# glove-pcb.net
KiCad netlist of a schematic drawn in EAGLE
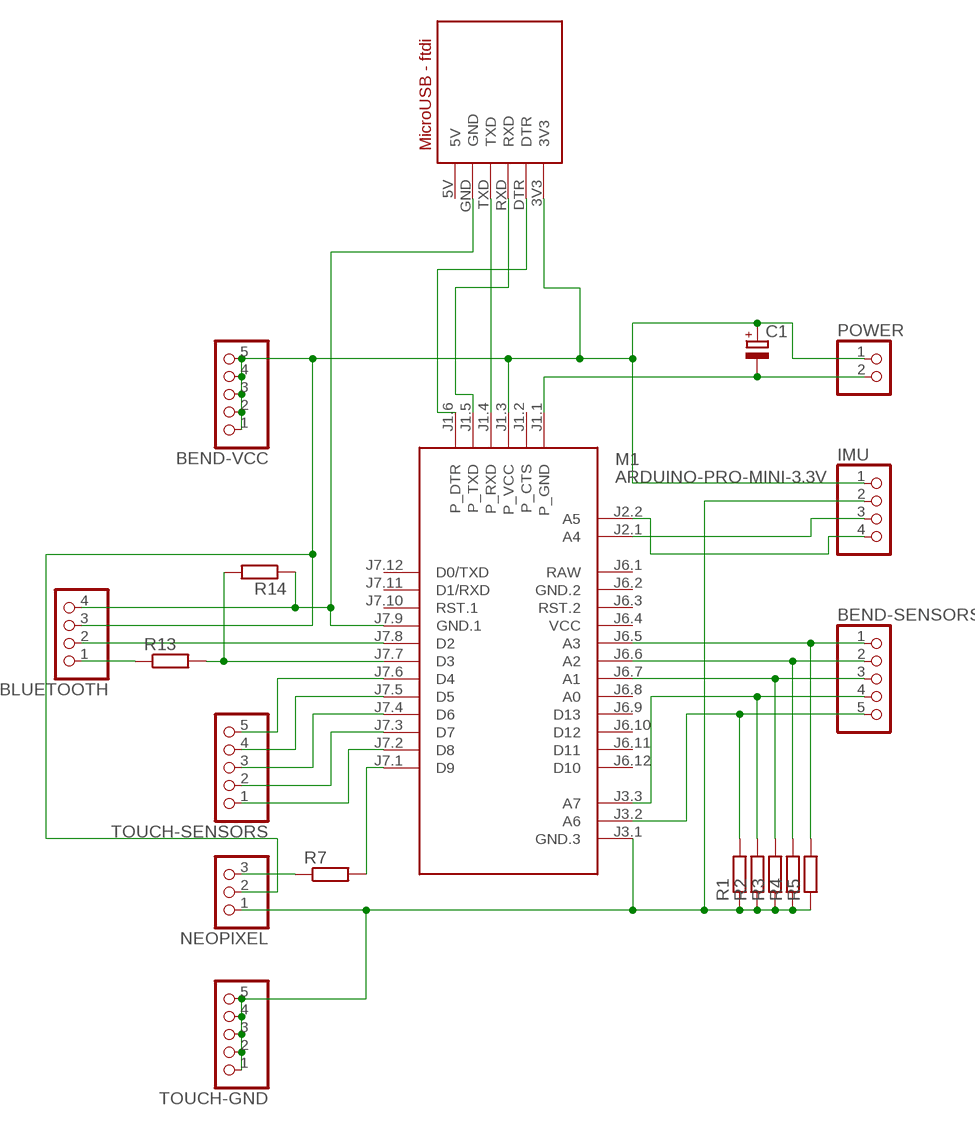
[diagram p0: schematic, sheet 1]

(export (version "E")
  (design (tool "Eeschema 10.0.6"))
  (components
    (comp (ref "BEND-SENSORS")
      (value "PINHD-1X5")
      (footprint "eagle-import:1X05")
      (libsource (lib "eagle-import") (part "PINHD-1X5"))
    )
    (comp (ref "BEND-VCC")
      (value "PINHD-1X5")
      (footprint "eagle-import:1X05")
      (libsource (lib "eagle-import") (part "PINHD-1X5"))
    )
    (comp (ref "BLUETOOTH")
      (value "PINHD-1X4")
      (footprint "eagle-import:1X04")
      (libsource (lib "eagle-import") (part "PINHD-1X4"))
    )
    (comp (ref "C1")
      (value "CPOL-EUE2-5")
      (footprint "eagle-import:E2-5")
      (libsource (lib "eagle-import") (part "CPOL-EUE2-5"))
    )
    (comp (ref "IMU")
      (value "PINHD-1X4")
      (footprint "eagle-import:1X04")
      (libsource (lib "eagle-import") (part "PINHD-1X4"))
    )
    (comp (ref "M1")
      (value "ARDUINO-PRO-MINI-3.3V")
      (footprint "eagle-import:ARDUINO-PRO-MINI")
      (libsource (lib "eagle-import") (part "ARDUINO-PRO-MINI-3.3V"))
    )
    (comp (ref "NEOPIXEL")
      (value "PINHD-1X3")
      (footprint "eagle-import:1X03")
      (libsource (lib "eagle-import") (part "PINHD-1X3"))
    )
    (comp (ref "POWER")
      (value "PINHD-1X2")
      (footprint "eagle-import:1X02")
      (libsource (lib "eagle-import") (part "PINHD-1X2"))
    )
    (comp (ref "R1")
      (value "R-EU_0204/7")
      (footprint "eagle-import:0204_7")
      (libsource (lib "eagle-import") (part "R-EU_0204/7"))
    )
    (comp (ref "R2")
      (value "R-EU_0204/7")
      (footprint "eagle-import:0204_7")
      (libsource (lib "eagle-import") (part "R-EU_0204/7"))
    )
    (comp (ref "R3")
      (value "R-EU_0204/7")
      (footprint "eagle-import:0204_7")
      (libsource (lib "eagle-import") (part "R-EU_0204/7"))
    )
    (comp (ref "R4")
      (value "R-EU_0204/7")
      (footprint "eagle-import:0204_7")
      (libsource (lib "eagle-import") (part "R-EU_0204/7"))
    )
    (comp (ref "R5")
      (value "R-EU_0204/7")
      (footprint "eagle-import:0204_7")
      (libsource (lib "eagle-import") (part "R-EU_0204/7"))
    )
    (comp (ref "R7")
      (value "R-EU_0204/2V")
      (footprint "eagle-import:0204V")
      (libsource (lib "eagle-import") (part "R-EU_0204/2V"))
    )
    (comp (ref "R13")
      (value "R-EU_0204/2V")
      (footprint "eagle-import:0204V")
      (libsource (lib "eagle-import") (part "R-EU_0204/2V"))
    )
    (comp (ref "R14")
      (value "R-EU_0204/2V")
      (footprint "eagle-import:0204V")
      (libsource (lib "eagle-import") (part "R-EU_0204/2V"))
    )
    (comp (ref "TOUCH-GND")
      (value "PINHD-1X5")
      (footprint "eagle-import:1X05")
      (libsource (lib "eagle-import") (part "PINHD-1X5"))
    )
    (comp (ref "TOUCH-SENSORS")
      (value "PINHD-1X5")
      (footprint "eagle-import:1X05")
      (libsource (lib "eagle-import") (part "PINHD-1X5"))
    )
    (comp (ref "U$1")
      (value "MICRO-USB-DEV")
      (footprint "eagle-import:MICRO-USB-PAC")
      (libsource (lib "eagle-import") (part "MICRO-USB-DEV"))
    )
  )
  (nets
    (net (code "1") (name "/5V") (class "Default")
      (node (ref "U$1") (pin "5V") (pinfunction "5V_5V") (pintype "power_in"))
    )
    (net (code "2") (name "/GND.2") (class "Default")
      (node (ref "M1") (pin "J6.2") (pinfunction "GND.2_J6.2") (pintype "power_in"))
    )
    (net (code "3") (name "/RAW") (class "Default")
      (node (ref "M1") (pin "J6.1") (pinfunction "RAW_J6.1") (pintype "power_in"))
    )
    (net (code "4") (name "/VCC") (class "Default")
      (node (ref "M1") (pin "J6.4") (pinfunction "VCC_J6.4") (pintype "power_in"))
    )
    (net (code "5") (name "Net-(BLUETOOTH-Pad1)") (class "Default")
      (node (ref "BLUETOOTH") (pin "1") (pinfunction "1_1") (pintype "passive"))
      (node (ref "R13") (pin "1") (pinfunction "1_1") (pintype "passive"))
    )
    (net (code "6") (name "Net-(M1-A1)") (class "Default")
      (node (ref "BEND-SENSORS") (pin "3") (pinfunction "3_3") (pintype "passive"))
      (node (ref "M1") (pin "J6.7") (pinfunction "A1_J6.7") (pintype "bidirectional"))
      (node (ref "R3") (pin "2") (pinfunction "2_2") (pintype "passive"))
    )
    (net (code "7") (name "Net-(M1-A2)") (class "Default")
      (node (ref "BEND-SENSORS") (pin "2") (pinfunction "2_2") (pintype "passive"))
      (node (ref "M1") (pin "J6.6") (pinfunction "A2_J6.6") (pintype "bidirectional"))
      (node (ref "R4") (pin "2") (pinfunction "2_2") (pintype "passive"))
    )
    (net (code "8") (name "Net-(M1-A3)") (class "Default")
      (node (ref "BEND-SENSORS") (pin "1") (pinfunction "1_1") (pintype "passive"))
      (node (ref "M1") (pin "J6.5") (pinfunction "A3_J6.5") (pintype "bidirectional"))
      (node (ref "R5") (pin "2") (pinfunction "2_2") (pintype "passive"))
    )
    (net (code "9") (name "Net-(M1-A4)") (class "Default")
      (node (ref "IMU") (pin "3") (pinfunction "3_3") (pintype "passive"))
      (node (ref "M1") (pin "J2.1") (pinfunction "A4_J2.1") (pintype "bidirectional"))
    )
    (net (code "10") (name "Net-(M1-A5)") (class "Default")
      (node (ref "IMU") (pin "4") (pinfunction "4_4") (pintype "passive"))
      (node (ref "M1") (pin "J2.2") (pinfunction "A5_J2.2") (pintype "bidirectional"))
    )
    (net (code "11") (name "Net-(M1-A6)") (class "Default")
      (node (ref "BEND-SENSORS") (pin "5") (pinfunction "5_5") (pintype "passive"))
      (node (ref "M1") (pin "J3.2") (pinfunction "A6_J3.2") (pintype "bidirectional"))
      (node (ref "R1") (pin "2") (pinfunction "2_2") (pintype "passive"))
    )
    (net (code "12") (name "Net-(M1-A7)") (class "Default")
      (node (ref "BEND-SENSORS") (pin "4") (pinfunction "4_4") (pintype "passive"))
      (node (ref "M1") (pin "J3.3") (pinfunction "A7_J3.3") (pintype "bidirectional"))
      (node (ref "R2") (pin "2") (pinfunction "2_2") (pintype "passive"))
    )
    (net (code "13") (name "Net-(M1-D2)") (class "Default")
      (node (ref "BLUETOOTH") (pin "2") (pinfunction "2_2") (pintype "passive"))
      (node (ref "M1") (pin "J7.8") (pinfunction "D2_J7.8") (pintype "bidirectional"))
    )
    (net (code "14") (name "Net-(M1-D3)") (class "Default")
      (node (ref "M1") (pin "J7.7") (pinfunction "D3_J7.7") (pintype "bidirectional"))
      (node (ref "R13") (pin "2") (pinfunction "2_2") (pintype "passive"))
      (node (ref "R14") (pin "2") (pinfunction "2_2") (pintype "passive"))
    )
    (net (code "15") (name "Net-(M1-D4)") (class "Default")
      (node (ref "M1") (pin "J7.6") (pinfunction "D4_J7.6") (pintype "bidirectional"))
      (node (ref "TOUCH-SENSORS") (pin "5") (pinfunction "5_5") (pintype "passive"))
    )
    (net (code "16") (name "Net-(M1-D5)") (class "Default")
      (node (ref "M1") (pin "J7.5") (pinfunction "D5_J7.5") (pintype "bidirectional"))
      (node (ref "TOUCH-SENSORS") (pin "4") (pinfunction "4_4") (pintype "passive"))
    )
    (net (code "17") (name "Net-(M1-D6)") (class "Default")
      (node (ref "M1") (pin "J7.4") (pinfunction "D6_J7.4") (pintype "bidirectional"))
      (node (ref "TOUCH-SENSORS") (pin "3") (pinfunction "3_3") (pintype "passive"))
    )
    (net (code "18") (name "Net-(M1-D7)") (class "Default")
      (node (ref "M1") (pin "J7.3") (pinfunction "D7_J7.3") (pintype "bidirectional"))
      (node (ref "TOUCH-SENSORS") (pin "2") (pinfunction "2_2") (pintype "passive"))
    )
    (net (code "19") (name "Net-(M1-D8)") (class "Default")
      (node (ref "M1") (pin "J7.2") (pinfunction "D8_J7.2") (pintype "bidirectional"))
      (node (ref "TOUCH-SENSORS") (pin "1") (pinfunction "1_1") (pintype "passive"))
    )
    (net (code "20") (name "Net-(M1-D9)") (class "Default")
      (node (ref "M1") (pin "J7.1") (pinfunction "D9_J7.1") (pintype "bidirectional"))
      (node (ref "R7") (pin "2") (pinfunction "2_2") (pintype "passive"))
    )
    (net (code "21") (name "Net-(M1-GND.1)") (class "Default")
      (node (ref "BLUETOOTH") (pin "4") (pinfunction "4_4") (pintype "passive"))
      (node (ref "M1") (pin "J7.9") (pinfunction "GND.1_J7.9") (pintype "power_in"))
      (node (ref "R14") (pin "1") (pinfunction "1_1") (pintype "passive"))
      (node (ref "U$1") (pin "GND") (pinfunction "GND_GND") (pintype "bidirectional"))
    )
    (net (code "22") (name "Net-(M1-GND.3)") (class "Default")
      (node (ref "IMU") (pin "2") (pinfunction "2_2") (pintype "passive"))
      (node (ref "M1") (pin "J3.1") (pinfunction "GND.3_J3.1") (pintype "bidirectional"))
      (node (ref "NEOPIXEL") (pin "1") (pinfunction "1_1") (pintype "passive"))
      (node (ref "R1") (pin "1") (pinfunction "1_1") (pintype "passive"))
      (node (ref "R2") (pin "1") (pinfunction "1_1") (pintype "passive"))
      (node (ref "R3") (pin "1") (pinfunction "1_1") (pintype "passive"))
      (node (ref "R4") (pin "1") (pinfunction "1_1") (pintype "passive"))
      (node (ref "R5") (pin "1") (pinfunction "1_1") (pintype "passive"))
      (node (ref "TOUCH-GND") (pin "1") (pinfunction "1_1") (pintype "passive"))
      (node (ref "TOUCH-GND") (pin "2") (pinfunction "2_2") (pintype "passive"))
      (node (ref "TOUCH-GND") (pin "3") (pinfunction "3_3") (pintype "passive"))
      (node (ref "TOUCH-GND") (pin "4") (pinfunction "4_4") (pintype "passive"))
      (node (ref "TOUCH-GND") (pin "5") (pinfunction "5_5") (pintype "passive"))
    )
    (net (code "23") (name "Net-(M1-P_DTR)") (class "Default")
      (node (ref "M1") (pin "J1.6") (pinfunction "P_DTR_J1.6") (pintype "bidirectional"))
      (node (ref "U$1") (pin "DTR") (pinfunction "DTR_DTR") (pintype "power_in"))
    )
    (net (code "24") (name "Net-(M1-P_GND)") (class "Default")
      (node (ref "C1") (pin "-") (pinfunction "-_-") (pintype "passive"))
      (node (ref "M1") (pin "J1.1") (pinfunction "P_GND_J1.1") (pintype "bidirectional"))
      (node (ref "POWER") (pin "2") (pinfunction "2_2") (pintype "passive"))
    )
    (net (code "25") (name "Net-(M1-P_RXD)") (class "Default")
      (node (ref "M1") (pin "J1.4") (pinfunction "P_RXD_J1.4") (pintype "bidirectional"))
      (node (ref "U$1") (pin "TXD") (pinfunction "TXD_TXD") (pintype "bidirectional"))
    )
    (net (code "26") (name "Net-(M1-P_TXD)") (class "Default")
      (node (ref "M1") (pin "J1.5") (pinfunction "P_TXD_J1.5") (pintype "bidirectional"))
      (node (ref "U$1") (pin "RXD") (pinfunction "RXD_RXD") (pintype "bidirectional"))
    )
    (net (code "27") (name "Net-(M1-P_VCC)") (class "Default")
      (node (ref "BEND-VCC") (pin "1") (pinfunction "1_1") (pintype "passive"))
      (node (ref "BEND-VCC") (pin "2") (pinfunction "2_2") (pintype "passive"))
      (node (ref "BEND-VCC") (pin "3") (pinfunction "3_3") (pintype "passive"))
      (node (ref "BEND-VCC") (pin "4") (pinfunction "4_4") (pintype "passive"))
      (node (ref "BEND-VCC") (pin "5") (pinfunction "5_5") (pintype "passive"))
      (node (ref "BLUETOOTH") (pin "3") (pinfunction "3_3") (pintype "passive"))
      (node (ref "C1") (pin "+") (pinfunction "+_+") (pintype "passive"))
      (node (ref "IMU") (pin "1") (pinfunction "1_1") (pintype "passive"))
      (node (ref "M1") (pin "J1.3") (pinfunction "P_VCC_J1.3") (pintype "bidirectional"))
      (node (ref "NEOPIXEL") (pin "2") (pinfunction "2_2") (pintype "passive"))
      (node (ref "POWER") (pin "1") (pinfunction "1_1") (pintype "passive"))
      (node (ref "U$1") (pin "3V3") (pinfunction "3V3_3V3") (pintype "power_in"))
    )
    (net (code "28") (name "Net-(NEOPIXEL-Pad3)") (class "Default")
      (node (ref "NEOPIXEL") (pin "3") (pinfunction "3_3") (pintype "passive"))
      (node (ref "R7") (pin "1") (pinfunction "1_1") (pintype "passive"))
    )
    (net (code "29") (name "unconnected-(M1-A0-PadJ6.8)") (class "Default")
      (node (ref "M1") (pin "J6.8") (pinfunction "A0_J6.8") (pintype "bidirectional"))
    )
    (net (code "30") (name "unconnected-(M1-D0{slash}TXD-PadJ7.12)") (class "Default")
      (node (ref "M1") (pin "J7.12") (pinfunction "D0/TXD_J7.12") (pintype "bidirectional"))
    )
    (net (code "31") (name "unconnected-(M1-D1{slash}RXD-PadJ7.11)") (class "Default")
      (node (ref "M1") (pin "J7.11") (pinfunction "D1/RXD_J7.11") (pintype "bidirectional"))
    )
    (net (code "32") (name "unconnected-(M1-D10-PadJ6.12)") (class "Default")
      (node (ref "M1") (pin "J6.12") (pinfunction "D10_J6.12") (pintype "bidirectional"))
    )
    (net (code "33") (name "unconnected-(M1-D11-PadJ6.11)") (class "Default")
      (node (ref "M1") (pin "J6.11") (pinfunction "D11_J6.11") (pintype "bidirectional"))
    )
    (net (code "34") (name "unconnected-(M1-D12-PadJ6.10)") (class "Default")
      (node (ref "M1") (pin "J6.10") (pinfunction "D12_J6.10") (pintype "bidirectional"))
    )
    (net (code "35") (name "unconnected-(M1-D13-PadJ6.9)") (class "Default")
      (node (ref "M1") (pin "J6.9") (pinfunction "D13_J6.9") (pintype "bidirectional"))
    )
    (net (code "36") (name "unconnected-(M1-P_CTS-PadJ1.2)") (class "Default")
      (node (ref "M1") (pin "J1.2") (pinfunction "P_CTS_J1.2") (pintype "bidirectional"))
    )
    (net (code "37") (name "unconnected-(M1-RST.1-PadJ7.10)") (class "Default")
      (node (ref "M1") (pin "J7.10") (pinfunction "RST.1_J7.10") (pintype "bidirectional"))
    )
    (net (code "38") (name "unconnected-(M1-RST.2-PadJ6.3)") (class "Default")
      (node (ref "M1") (pin "J6.3") (pinfunction "RST.2_J6.3") (pintype "bidirectional"))
    )
  )
)
